# eLight.net
KiCad netlist of a schematic drawn in EasyEDA Pro
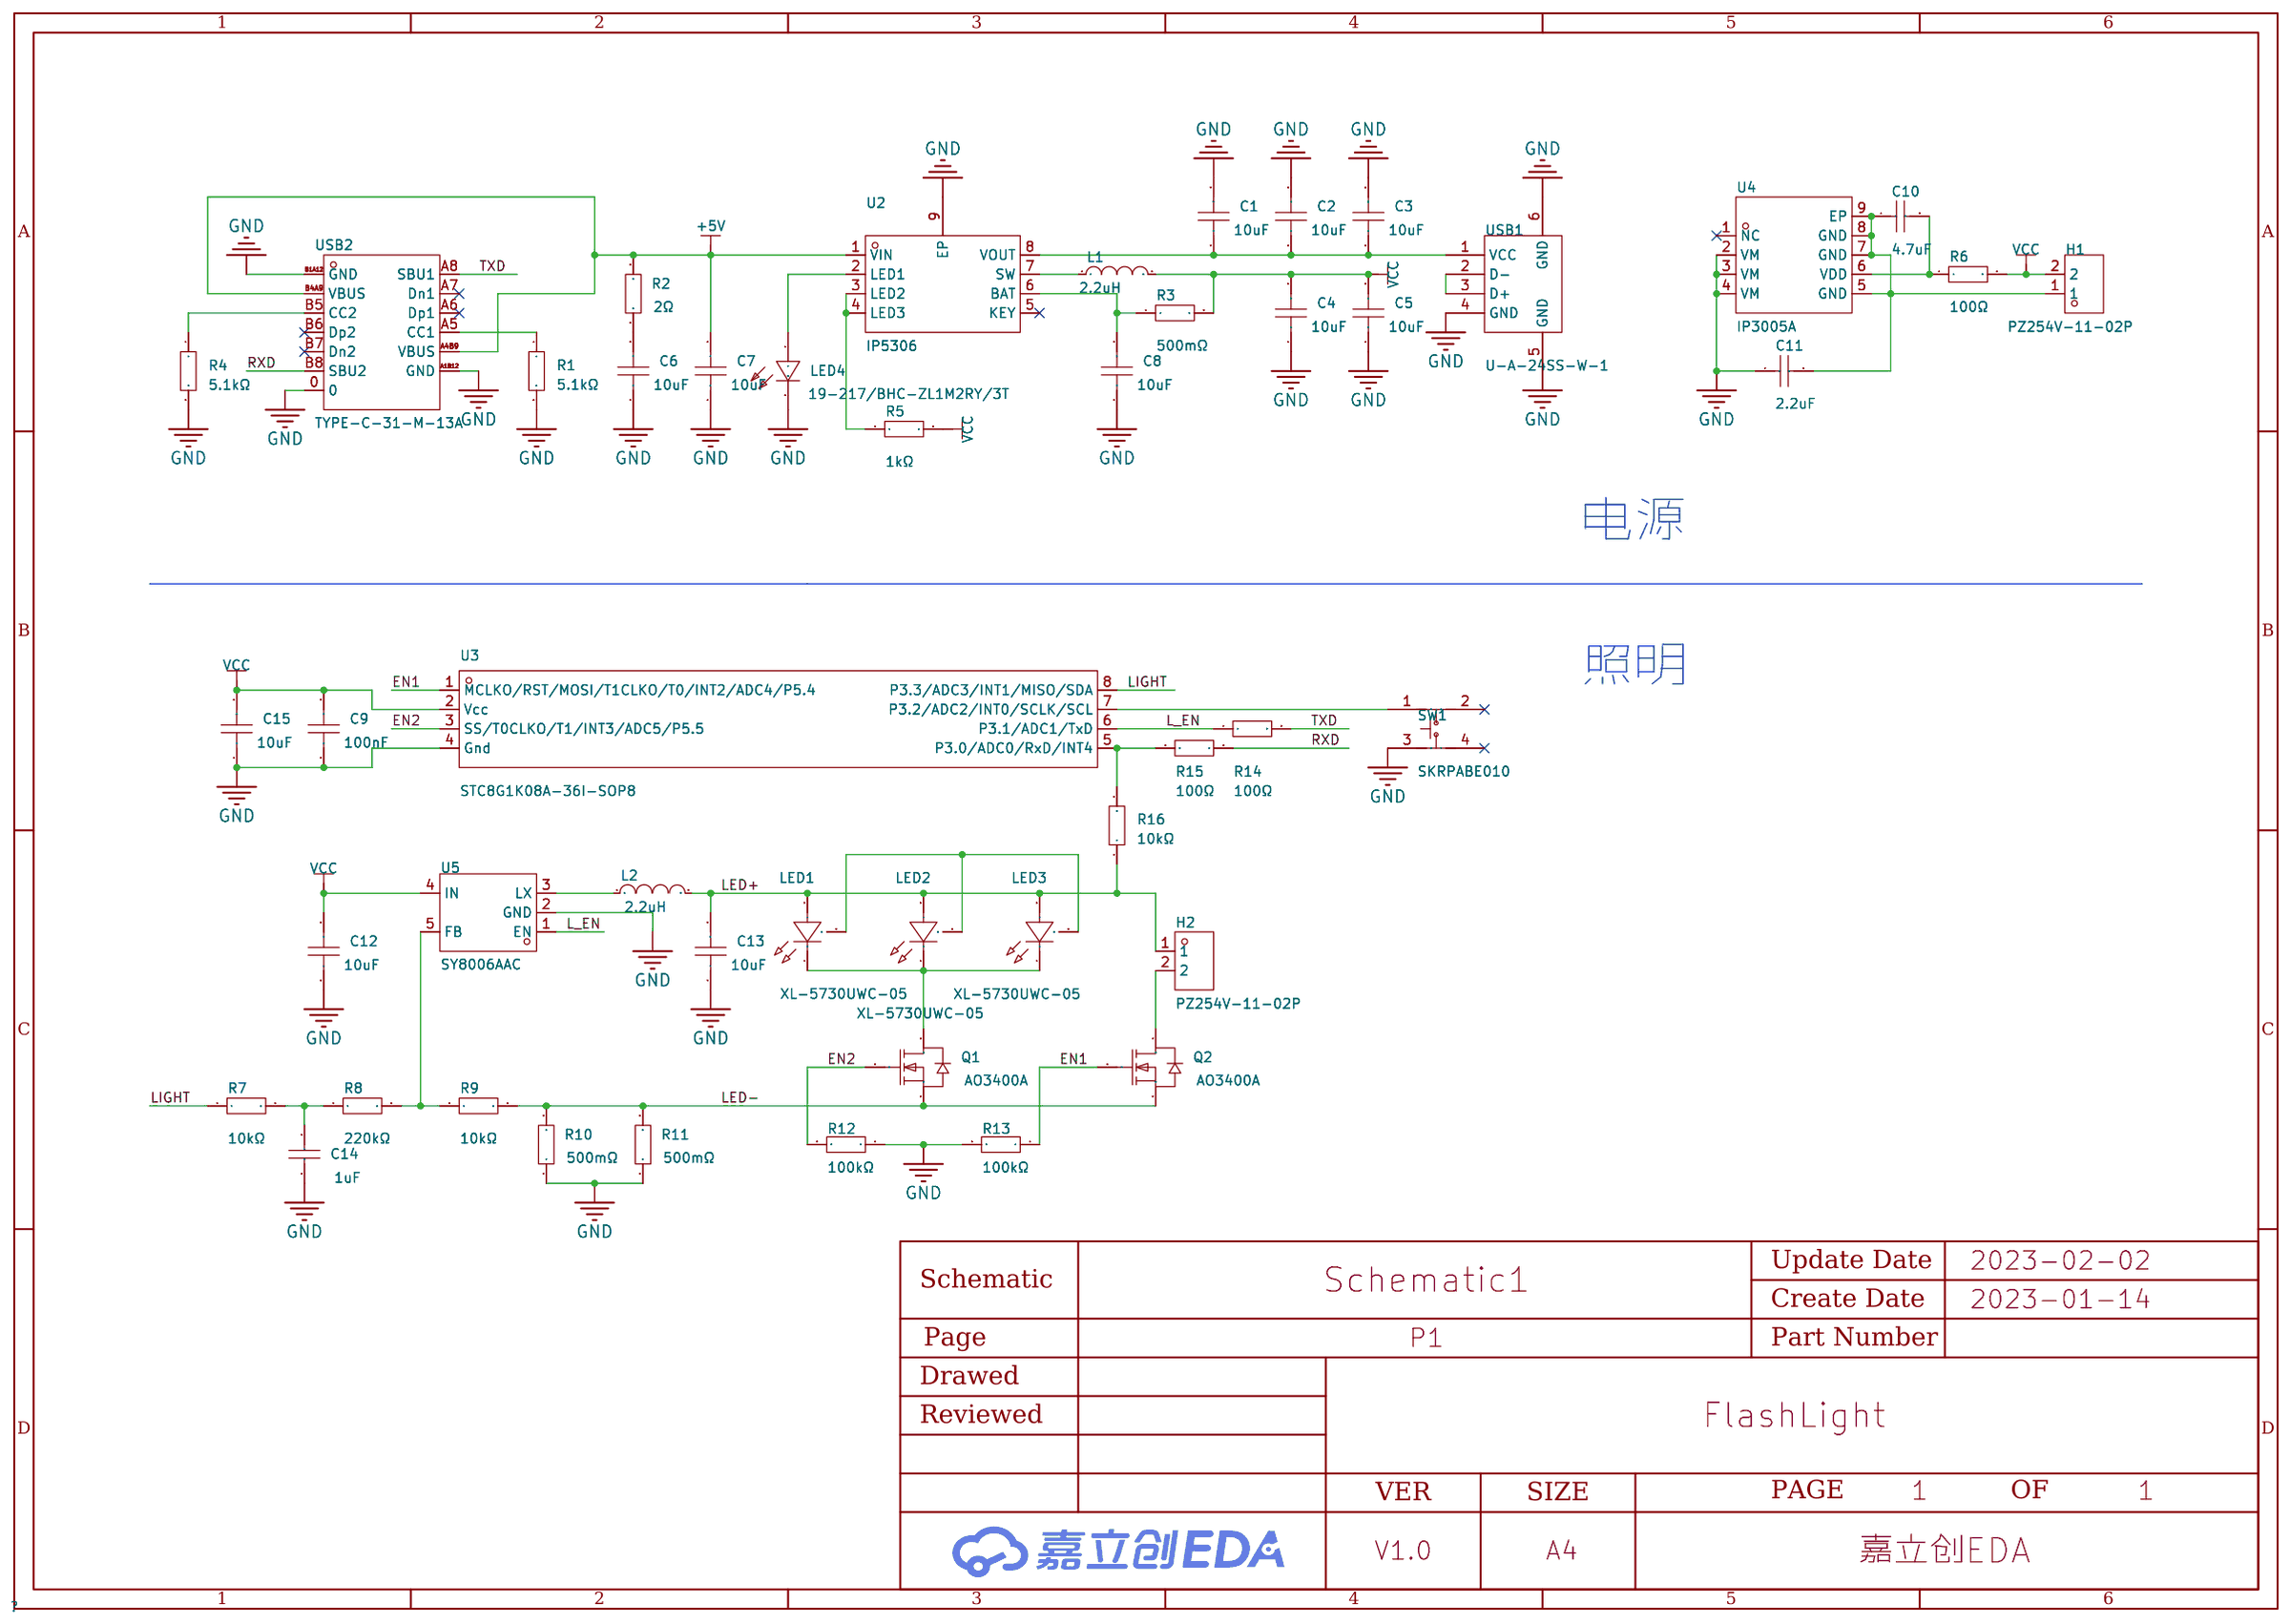
[diagram p0: schematic sheet]

(export (version "E")
  (design (tool "Eeschema 10.0.6"))
  (components
    (comp (ref "C1")
      (value "10uF")
      (footprint "easyedapro:C0603")
      (description "容值:10uF;精度:±10%;额定电压:10V;材质(温度系数):X5R;")
      (fields
        (field (name "Manufacturer Part") "CL10A106KP8NNNC")
        (field (name "Manufacturer") "SAMSUNG(三星)")
      )
      (libsource (lib "easyedapro") (part "CL10A106KP8NNNC"))
    )
    (comp (ref "C2")
      (value "10uF")
      (footprint "easyedapro:C0603")
      (description "容值:10uF;精度:±10%;额定电压:10V;材质(温度系数):X5R;")
      (fields
        (field (name "Manufacturer Part") "CL10A106KP8NNNC")
        (field (name "Manufacturer") "SAMSUNG(三星)")
      )
      (libsource (lib "easyedapro") (part "CL10A106KP8NNNC"))
    )
    (comp (ref "C3")
      (value "10uF")
      (footprint "easyedapro:C0603")
      (description "容值:10uF;精度:±10%;额定电压:10V;材质(温度系数):X5R;")
      (fields
        (field (name "Manufacturer Part") "CL10A106KP8NNNC")
        (field (name "Manufacturer") "SAMSUNG(三星)")
      )
      (libsource (lib "easyedapro") (part "CL10A106KP8NNNC"))
    )
    (comp (ref "C4")
      (value "10uF")
      (footprint "easyedapro:C0603")
      (description "容值:10uF;精度:±10%;额定电压:10V;材质(温度系数):X5R;")
      (fields
        (field (name "Manufacturer Part") "CL10A106KP8NNNC")
        (field (name "Manufacturer") "SAMSUNG(三星)")
      )
      (libsource (lib "easyedapro") (part "CL10A106KP8NNNC"))
    )
    (comp (ref "C5")
      (value "10uF")
      (footprint "easyedapro:C0603")
      (description "容值:10uF;精度:±10%;额定电压:10V;材质(温度系数):X5R;")
      (fields
        (field (name "Manufacturer Part") "CL10A106KP8NNNC")
        (field (name "Manufacturer") "SAMSUNG(三星)")
      )
      (libsource (lib "easyedapro") (part "CL10A106KP8NNNC"))
    )
    (comp (ref "C6")
      (value "10uF")
      (footprint "easyedapro:C0603")
      (description "容值:10uF;精度:±10%;额定电压:10V;材质(温度系数):X5R;")
      (fields
        (field (name "Manufacturer Part") "CL10A106KP8NNNC")
        (field (name "Manufacturer") "SAMSUNG(三星)")
      )
      (libsource (lib "easyedapro") (part "CL10A106KP8NNNC"))
    )
    (comp (ref "C7")
      (value "10uF")
      (footprint "easyedapro:C0603")
      (description "容值:10uF;精度:±10%;额定电压:10V;材质(温度系数):X5R;")
      (fields
        (field (name "Manufacturer Part") "CL10A106KP8NNNC")
        (field (name "Manufacturer") "SAMSUNG(三星)")
      )
      (libsource (lib "easyedapro") (part "CL10A106KP8NNNC"))
    )
    (comp (ref "C8")
      (value "10uF")
      (footprint "easyedapro:C0603")
      (description "容值:10uF;精度:±10%;额定电压:10V;材质(温度系数):X5R;")
      (fields
        (field (name "Manufacturer Part") "CL10A106KP8NNNC")
        (field (name "Manufacturer") "SAMSUNG(三星)")
      )
      (libsource (lib "easyedapro") (part "CL10A106KP8NNNC"))
    )
    (comp (ref "C9")
      (value "100nF")
      (footprint "easyedapro:C0603")
      (description "容值:100nF;精度:±10%;额定电压:50V;材质(温度系数):X7R;")
      (fields
        (field (name "Manufacturer Part") "CC0603KRX7R9BB104")
        (field (name "Manufacturer") "YAGEO(国巨)")
      )
      (libsource (lib "easyedapro") (part "CC0603KRX7R9BB104"))
    )
    (comp (ref "C10")
      (value "4.7uF")
      (footprint "easyedapro:C0603")
      (description "容值:4.7uF;精度:±10%;额定电压:16V;材质(温度系数):X5R;")
      (fields
        (field (name "Manufacturer Part") "CL10A475KO8NNNC")
        (field (name "Manufacturer") "SAMSUNG(三星)")
      )
      (libsource (lib "easyedapro") (part "CL10A475KO8NNNC"))
    )
    (comp (ref "C11")
      (value "2.2uF")
      (footprint "easyedapro:C0603")
      (description "容值:2.2uF;精度:±10%;额定电压:16V;材质(温度系数):X5R;")
      (fields
        (field (name "Manufacturer Part") "CL10A225KO8NNNC")
        (field (name "Manufacturer") "SAMSUNG(三星)")
      )
      (libsource (lib "easyedapro") (part "CL10A225KO8NNNC"))
    )
    (comp (ref "C12")
      (value "10uF")
      (footprint "easyedapro:C0603")
      (description "容值:10uF;精度:±10%;额定电压:10V;材质(温度系数):X5R;")
      (fields
        (field (name "Manufacturer Part") "CL10A106KP8NNNC")
        (field (name "Manufacturer") "SAMSUNG(三星)")
      )
      (libsource (lib "easyedapro") (part "CL10A106KP8NNNC"))
    )
    (comp (ref "C13")
      (value "10uF")
      (footprint "easyedapro:C0603")
      (description "容值:10uF;精度:±10%;额定电压:10V;材质(温度系数):X5R;")
      (fields
        (field (name "Manufacturer Part") "CL10A106KP8NNNC")
        (field (name "Manufacturer") "SAMSUNG(三星)")
      )
      (libsource (lib "easyedapro") (part "CL10A106KP8NNNC"))
    )
    (comp (ref "C14")
      (value "1uF")
      (footprint "easyedapro:C0603")
      (description "容值:1uF;精度:±10%;额定电压:50V;材质(温度系数):X5R;")
      (fields
        (field (name "Manufacturer Part") "CL10A105KB8NNNC")
        (field (name "Manufacturer") "SAMSUNG(三星)")
      )
      (libsource (lib "easyedapro") (part "CL10A105KB8NNNC"))
    )
    (comp (ref "C15")
      (value "10uF")
      (footprint "easyedapro:C0603")
      (description "容值:10uF;精度:±10%;额定电压:10V;材质(温度系数):X5R;")
      (fields
        (field (name "Manufacturer Part") "CL10A106KP8NNNC")
        (field (name "Manufacturer") "SAMSUNG(三星)")
      )
      (libsource (lib "easyedapro") (part "CL10A106KP8NNNC"))
    )
    (comp (ref "H1")
      (value "PZ254V-11-02P")
      (footprint "easyedapro:HDR-TH_2P-P2.54-V-M")
      (fields (field (name "Manufacturer") "XFCN(兴飞)"))
      (libsource (lib "easyedapro") (part "PZ254V-11-02P"))
    )
    (comp (ref "H2")
      (value "PZ254V-11-02P")
      (footprint "easyedapro:HDR-TH_2P-P2.54-V-M")
      (fields (field (name "Manufacturer") "XFCN(兴飞)"))
      (libsource (lib "easyedapro") (part "PZ254V-11-02P"))
    )
    (comp (ref "L1")
      (value "2.2uH")
      (footprint "easyedapro:IND-SMD_L7.3-W6.6")
      (description "电感值:2.2uH;精度:±20%;额定电流:8A;饱和电流(Isat):12A;直流电阻(DCR):17mΩ;")
      (fields (field (name "Manufacturer Part") "MCS0630-2R2MPY1") (field (name "Manufacturer") "PSA(信昌电陶)"))
      (libsource (lib "easyedapro") (part "MCS0630-2R2MPY1"))
    )
    (comp (ref "L2")
      (value "2.2uH")
      (footprint "easyedapro:IND-SMD_L4.5-W4.0-1")
      (description "电感值:2.2uH;精度:±20%;额定电流:3A;直流电阻(DCR):52mΩ;")
      (fields (field (name "Manufacturer Part") "MCS0420-2R2MN2") (field (name "Manufacturer") "PSA(信昌电陶)"))
      (libsource (lib "easyedapro") (part "MCS0420-2R2MN2"))
    )
    (comp (ref "LED1")
      (value "XL-5730UWC-05")
      (footprint "easyedapro:LED-SMD_3P-L5.7-W3.0-RD")
      (fields (field (name "Manufacturer") "XINGLIGHT(成兴光)"))
      (libsource (lib "easyedapro") (part "XL-5730UWC-05"))
    )
    (comp (ref "LED2")
      (value "XL-5730UWC-05")
      (footprint "easyedapro:LED-SMD_3P-L5.7-W3.0-RD")
      (fields (field (name "Manufacturer") "XINGLIGHT(成兴光)"))
      (libsource (lib "easyedapro") (part "XL-5730UWC-05"))
    )
    (comp (ref "LED3")
      (value "XL-5730UWC-05")
      (footprint "easyedapro:LED-SMD_3P-L5.7-W3.0-RD")
      (fields (field (name "Manufacturer") "XINGLIGHT(成兴光)"))
      (libsource (lib "easyedapro") (part "XL-5730UWC-05"))
    )
    (comp (ref "LED4")
      (value "19-217/BHC-ZL1M2RY/3T")
      (footprint "easyedapro:LED0603-R-RD_BLUE")
      (description "照明颜色:蓝色;主波长/色坐标:465~475nm;")
      (fields (field (name "Manufacturer") "EVERLIGHT(亿光)"))
      (libsource (lib "easyedapro") (part "19-217/BHC-ZL1M2RY/3T"))
    )
    (comp (ref "Q1")
      (value "AO3400A")
      (footprint "easyedapro:SOT-23-3_L2.9-W1.6-P1.90-LS2.8-BR")
      (fields (field (name "Manufacturer") "AOS"))
      (libsource (lib "easyedapro") (part "AO3400A"))
    )
    (comp (ref "Q2")
      (value "AO3400A")
      (footprint "easyedapro:SOT-23-3_L2.9-W1.6-P1.90-LS2.8-BR")
      (fields (field (name "Manufacturer") "AOS"))
      (libsource (lib "easyedapro") (part "AO3400A"))
    )
    (comp (ref "R1")
      (value "5.1kΩ")
      (footprint "easyedapro:R0603")
      (description "电阻类型:厚膜电阻;阻值:5.1kΩ;精度:±1%;功率:100mW;温度系数:±100ppm/℃;最大工作电压:75V;工作温度范围:-55℃~+155℃;")
      (fields
        (field (name "Manufacturer Part") "0603WAF5101T5E")
        (field (name "Manufacturer") "UNI-ROYAL(厚声)")
      )
      (libsource (lib "easyedapro") (part "0603WAF5101T5E"))
    )
    (comp (ref "R2")
      (value "2Ω")
      (footprint "easyedapro:R0603")
      (description "电阻类型:厚膜电阻;阻值:2Ω;精度:±1%;功率:100mW;温度系数:±400ppm/℃;最大工作电压:75V;工作温度范围:-55℃~+155℃;")
      (fields
        (field (name "Manufacturer Part") "0603WAF200KT5E")
        (field (name "Manufacturer") "UNI-ROYAL(厚声)")
      )
      (libsource (lib "easyedapro") (part "0603WAF200KT5E"))
    )
    (comp (ref "R3")
      (value "500mΩ")
      (footprint "easyedapro:R0603")
      (description "电阻类型:厚膜电阻;阻值:510mΩ;精度:±1%;功率:100mW;温度系数:±800ppm/°C;最大工作电压:75V;工作温度范围:-55°C~+155°C;")
      (fields
        (field (name "Manufacturer Part") "0603WAF500LT5E")
        (field (name "Manufacturer") "UNI-ROYAL(厚声)")
      )
      (libsource (lib "easyedapro") (part "0603WAF510LT5E"))
    )
    (comp (ref "R4")
      (value "5.1kΩ")
      (footprint "easyedapro:R0603")
      (description "电阻类型:厚膜电阻;阻值:5.1kΩ;精度:±1%;功率:100mW;温度系数:±100ppm/°C;最大工作电压:75V;工作温度范围:-55°C~+155°C;")
      (fields
        (field (name "Manufacturer Part") "0603WAF5101T5E")
        (field (name "Manufacturer") "UNI-ROYAL(厚声)")
      )
      (libsource (lib "easyedapro") (part "0603WAF5101T5E"))
    )
    (comp (ref "R5")
      (value "1kΩ")
      (footprint "easyedapro:R0603")
      (description "电阻类型:厚膜电阻;阻值:1kΩ;精度:±1%;功率:100mW;温度系数:±100ppm/°C;最大工作电压:75V;工作温度范围:-55°C~+155°C;")
      (fields
        (field (name "Manufacturer Part") "0603WAF1001T5E")
        (field (name "Manufacturer") "UNI-ROYAL(厚声)")
      )
      (libsource (lib "easyedapro") (part "0603WAF1001T5E"))
    )
    (comp (ref "R6")
      (value "100Ω")
      (footprint "easyedapro:R0603")
      (description "电阻类型:厚膜电阻;阻值:100Ω;精度:±1%;功率:100mW;温度系数:±200ppm/°C;最大工作电压:75V;工作温度范围:-55°C~+155°C;")
      (fields
        (field (name "Manufacturer Part") "0603WAF1000T5E")
        (field (name "Manufacturer") "UNI-ROYAL(厚声)")
      )
      (libsource (lib "easyedapro") (part "0603WAF1000T5E"))
    )
    (comp (ref "R7")
      (value "10kΩ")
      (footprint "easyedapro:R0603")
      (description "电阻类型:厚膜电阻;阻值:10kΩ;精度:±1%;功率:100mW;温度系数:±100ppm/°C;最大工作电压:75V;工作温度范围:-55°C~+155°C;")
      (fields
        (field (name "Manufacturer Part") "0603WAF1002T5E")
        (field (name "Manufacturer") "UNI-ROYAL(厚声)")
      )
      (libsource (lib "easyedapro") (part "0603WAF1002T5E"))
    )
    (comp (ref "R8")
      (value "220kΩ")
      (footprint "easyedapro:R0603")
      (description "电阻类型:厚膜电阻;阻值:100kΩ;精度:±1%;功率:100mW;温度系数:±100ppm/°C;最大工作电压:75V;工作温度范围:-55°C~+155°C;")
      (fields
        (field (name "Manufacturer Part") "0603WAF2203T5E")
        (field (name "Manufacturer") "UNI-ROYAL(厚声)")
      )
      (libsource (lib "easyedapro") (part "0603WAF1003T5E"))
    )
    (comp (ref "R9")
      (value "10kΩ")
      (footprint "easyedapro:R0603")
      (description "电阻类型:厚膜电阻;阻值:10kΩ;精度:±1%;功率:100mW;温度系数:±100ppm/°C;最大工作电压:75V;工作温度范围:-55°C~+155°C;")
      (fields
        (field (name "Manufacturer Part") "0603WAF1002T5E")
        (field (name "Manufacturer") "UNI-ROYAL(厚声)")
      )
      (libsource (lib "easyedapro") (part "0603WAF1002T5E"))
    )
    (comp (ref "R10")
      (value "500mΩ")
      (footprint "easyedapro:R0805")
      (description "电阻类型:厚膜电阻;阻值:500mΩ;精度:±1%;功率:125mW;温度系数:±800ppm/℃;最大工作电压:150V;工作温度范围:-55℃~+155℃;")
      (fields
        (field (name "Manufacturer Part") "0805W8F500LT5E")
        (field (name "Manufacturer") "UNI-ROYAL(厚声)")
      )
      (libsource (lib "easyedapro") (part "0805W8F510LT5E"))
    )
    (comp (ref "R11")
      (value "500mΩ")
      (footprint "easyedapro:R0805")
      (description "电阻类型:厚膜电阻;阻值:510mΩ;精度:±1%;功率:125mW;温度系数:±800ppm/°C;最大工作电压:150V;工作温度范围:-55°C~+155°C;")
      (fields
        (field (name "Manufacturer Part") "0805W8F500LT5E")
        (field (name "Manufacturer") "UNI-ROYAL(厚声)")
      )
      (libsource (lib "easyedapro") (part "0805W8F510LT5E"))
    )
    (comp (ref "R12")
      (value "100kΩ")
      (footprint "easyedapro:R0603")
      (description "电阻类型:厚膜电阻;阻值:10kΩ;精度:±1%;功率:100mW;温度系数:±100ppm/°C;最大工作电压:75V;工作温度范围:-55°C~+155°C;")
      (fields
        (field (name "Manufacturer Part") "0603WAF1003T5E")
        (field (name "Manufacturer") "UNI-ROYAL(厚声)")
      )
      (libsource (lib "easyedapro") (part "0603WAF1002T5E"))
    )
    (comp (ref "R13")
      (value "100kΩ")
      (footprint "easyedapro:R0603")
      (description "电阻类型:厚膜电阻;阻值:10kΩ;精度:±1%;功率:100mW;温度系数:±100ppm/°C;最大工作电压:75V;工作温度范围:-55°C~+155°C;")
      (fields
        (field (name "Manufacturer Part") "0603WAF1003T5E")
        (field (name "Manufacturer") "UNI-ROYAL(厚声)")
      )
      (libsource (lib "easyedapro") (part "0603WAF1002T5E"))
    )
    (comp (ref "R14")
      (value "100Ω")
      (footprint "easyedapro:R0603")
      (description "电阻类型:厚膜电阻;阻值:100Ω;精度:±1%;功率:100mW;温度系数:±200ppm/°C;最大工作电压:75V;工作温度范围:-55°C~+155°C;")
      (fields
        (field (name "Manufacturer Part") "0603WAF1000T5E")
        (field (name "Manufacturer") "UNI-ROYAL(厚声)")
      )
      (libsource (lib "easyedapro") (part "0603WAF1000T5E"))
    )
    (comp (ref "R15")
      (value "100Ω")
      (footprint "easyedapro:R0603")
      (description "电阻类型:厚膜电阻;阻值:100Ω;精度:±1%;功率:100mW;温度系数:±200ppm/°C;最大工作电压:75V;工作温度范围:-55°C~+155°C;")
      (fields
        (field (name "Manufacturer Part") "0603WAF1000T5E")
        (field (name "Manufacturer") "UNI-ROYAL(厚声)")
      )
      (libsource (lib "easyedapro") (part "0603WAF1000T5E"))
    )
    (comp (ref "R16")
      (value "10kΩ")
      (footprint "easyedapro:R0603")
      (description "电阻类型:厚膜电阻;阻值:10kΩ;精度:±1%;功率:100mW;温度系数:±100ppm/°C;最大工作电压:75V;工作温度范围:-55°C~+155°C;")
      (fields
        (field (name "Manufacturer Part") "0603WAF1002T5E")
        (field (name "Manufacturer") "UNI-ROYAL(厚声)")
      )
      (libsource (lib "easyedapro") (part "0603WAF1002T5E"))
    )
    (comp (ref "SW1")
      (value "SKRPABE010")
      (footprint "easyedapro:KEY-SMD_4P-L4.2-W3.2-P2.20-LS4.6")
      (description "触点电流:50mA;额定电压(DC):16V;电路结构:单刀单掷;按钮作用方向:顶部触动;致动器样式:椭圆形按钮;照明颜色:-;开关长度:4.2mm;开关宽度:3.2mm;开关高度:2.5mm;")
      (fields (field (name "Manufacturer") "ALPSALPINE(阿尔卑斯阿尔派)"))
      (libsource (lib "easyedapro") (part "SKRPABE010"))
    )
    (comp (ref "U2")
      (value "IP5306")
      (footprint "easyedapro:ESOP-8_L4.9-W3.9-P1.27-LS6.0-BL-EP")
      (description "2.1A充电2.4A放电高集成度移动电源SOC")
      (fields (field (name "Manufacturer") "INJOINIC(英集芯)"))
      (libsource (lib "easyedapro") (part "IP5306"))
    )
    (comp (ref "U3")
      (value "STC8G1K08A-36I-SOP8")
      (footprint "easyedapro:SOP-8_L5.0-W4.0-P1.27-LS6.0-BL")
      (fields (field (name "Manufacturer") "STC(宏晶)"))
      (libsource (lib "easyedapro") (part "STC8G1K08A-36I-SOP8"))
    )
    (comp (ref "U4")
      (value "IP3005A")
      (footprint "easyedapro:ESOP-8_L4.9-W3.9-P1.27-LS6.0-BL-EP")
      (description "过充电压:4.28V,过充恢复电压:4.1V,高精度内置MOSFET单节锂电池保护IC")
      (fields (field (name "Manufacturer") "INJOINIC(英集芯)"))
      (libsource (lib "easyedapro") (part "IP3005A"))
    )
    (comp (ref "U5")
      (value "SY8006AAC")
      (footprint "easyedapro:SOT-23-5_L3.0-W1.6-P0.95-LS2.8-BR")
      (fields (field (name "Manufacturer") "silergy(矽力杰)"))
      (libsource (lib "easyedapro") (part "SY8006AAC"))
    )
    (comp (ref "USB1")
      (value "U-A-24SS-W-1")
      (footprint "easyedapro:USB-A-SMD_U-A-24SS-W-1")
      (description "连接器类型:Type-A;标准:USB 2.0;公母:母座;触点数量:4;端口数量:1;额定电流 - 电源:-;")
      (fields (field (name "Manufacturer") "韩国韩荣"))
      (libsource (lib "easyedapro") (part "U-A-24SS-W-1"))
    )
    (comp (ref "USB2")
      (value "TYPE-C-31-M-13A")
      (footprint "easyedapro:USB-C-SMD_TYPE-C-31-M-13A-1")
      (fields (field (name "Manufacturer") "韩国韩荣"))
      (libsource (lib "easyedapro") (part "TYPE-C-31-M-13A"))
    )
  )
  (nets
    (net (code "1") (name "+5V") (class "Default")
      (node (ref "C7") (pin "2") (pinfunction "2_2") (pintype "input"))
      (node (ref "R2") (pin "2") (pinfunction "2_2") (pintype "input"))
      (node (ref "U2") (pin "1") (pinfunction "VIN_1") (pintype "input"))
      (node (ref "USB2") (pin "A4B9") (pinfunction "VBUS_A4B9") (pintype "input"))
      (node (ref "USB2") (pin "B4A9") (pinfunction "VBUS_B4A9") (pintype "input"))
    )
    (net (code "2") (name "/EN1") (class "Default")
      (node (ref "Q2") (pin "1") (pinfunction "G_1") (pintype "input"))
      (node (ref "R13") (pin "1") (pinfunction "1_1") (pintype "input"))
      (node (ref "U3") (pin "1") (pinfunction "MCLKO/RST/MOSI/T1CLKO/T0/INT2/ADC4/P5.4_1") (pintype "input"))
    )
    (net (code "3") (name "/EN2") (class "Default")
      (node (ref "Q1") (pin "1") (pinfunction "G_1") (pintype "input"))
      (node (ref "R12") (pin "2") (pinfunction "2_2") (pintype "input"))
      (node (ref "U3") (pin "3") (pinfunction "SS/T0CLKO/T1/INT3/ADC5/P5.5_3") (pintype "input"))
    )
    (net (code "4") (name "/LED+") (class "Default")
      (node (ref "C13") (pin "2") (pinfunction "2_2") (pintype "input"))
      (node (ref "H2") (pin "1") (pinfunction "1_1") (pintype "input"))
      (node (ref "L2") (pin "2") (pinfunction "2_2") (pintype "input"))
      (node (ref "LED1") (pin "2") (pinfunction "A_2") (pintype "input"))
      (node (ref "LED2") (pin "2") (pinfunction "A_2") (pintype "input"))
      (node (ref "LED3") (pin "2") (pinfunction "A_2") (pintype "input"))
      (node (ref "R16") (pin "1") (pinfunction "1_1") (pintype "input"))
    )
    (net (code "5") (name "/LED-") (class "Default")
      (node (ref "Q1") (pin "2") (pinfunction "S_2") (pintype "input"))
      (node (ref "Q2") (pin "2") (pinfunction "S_2") (pintype "input"))
      (node (ref "R10") (pin "2") (pinfunction "2_2") (pintype "input"))
      (node (ref "R11") (pin "2") (pinfunction "2_2") (pintype "input"))
      (node (ref "R9") (pin "2") (pinfunction "2_2") (pintype "input"))
    )
    (net (code "6") (name "/LIGHT") (class "Default")
      (node (ref "R7") (pin "1") (pinfunction "1_1") (pintype "input"))
      (node (ref "U3") (pin "8") (pinfunction "P3.3/ADC3/INT1/MISO/SDA_8") (pintype "input"))
    )
    (net (code "7") (name "/L_EN") (class "Default")
      (node (ref "R14") (pin "1") (pinfunction "1_1") (pintype "input"))
      (node (ref "U3") (pin "6") (pinfunction "P3.1/ADC1/TxD_6") (pintype "input"))
      (node (ref "U5") (pin "1") (pinfunction "EN_1") (pintype "input"))
    )
    (net (code "8") (name "/RXD") (class "Default")
      (node (ref "R15") (pin "2") (pinfunction "2_2") (pintype "input"))
      (node (ref "USB2") (pin "B8") (pinfunction "SBU2_B8") (pintype "input"))
    )
    (net (code "9") (name "/TXD") (class "Default")
      (node (ref "R14") (pin "2") (pinfunction "2_2") (pintype "input"))
      (node (ref "USB2") (pin "A8") (pinfunction "SBU1_A8") (pintype "input"))
    )
    (net (code "10") (name "GND") (class "Default")
      (node (ref "C1") (pin "2") (pinfunction "2_2") (pintype "input"))
      (node (ref "C11") (pin "1") (pinfunction "1_1") (pintype "input"))
      (node (ref "C12") (pin "1") (pinfunction "1_1") (pintype "input"))
      (node (ref "C13") (pin "1") (pinfunction "1_1") (pintype "input"))
      (node (ref "C14") (pin "1") (pinfunction "1_1") (pintype "input"))
      (node (ref "C15") (pin "1") (pinfunction "1_1") (pintype "input"))
      (node (ref "C2") (pin "2") (pinfunction "2_2") (pintype "input"))
      (node (ref "C3") (pin "2") (pinfunction "2_2") (pintype "input"))
      (node (ref "C4") (pin "1") (pinfunction "1_1") (pintype "input"))
      (node (ref "C5") (pin "1") (pinfunction "1_1") (pintype "input"))
      (node (ref "C6") (pin "1") (pinfunction "1_1") (pintype "input"))
      (node (ref "C7") (pin "1") (pinfunction "1_1") (pintype "input"))
      (node (ref "C8") (pin "1") (pinfunction "1_1") (pintype "input"))
      (node (ref "C9") (pin "1") (pinfunction "1_1") (pintype "input"))
      (node (ref "LED4") (pin "2") (pinfunction "C_2") (pintype "input"))
      (node (ref "R1") (pin "2") (pinfunction "2_2") (pintype "input"))
      (node (ref "R10") (pin "1") (pinfunction "1_1") (pintype "input"))
      (node (ref "R11") (pin "1") (pinfunction "1_1") (pintype "input"))
      (node (ref "R12") (pin "1") (pinfunction "1_1") (pintype "input"))
      (node (ref "R13") (pin "2") (pinfunction "2_2") (pintype "input"))
      (node (ref "R4") (pin "2") (pinfunction "2_2") (pintype "input"))
      (node (ref "SW1") (pin "3") (pinfunction "3_3") (pintype "input"))
      (node (ref "U2") (pin "9") (pinfunction "EP_9") (pintype "input"))
      (node (ref "U3") (pin "4") (pinfunction "Gnd_4") (pintype "input"))
      (node (ref "U4") (pin "2") (pinfunction "VM_2") (pintype "input"))
      (node (ref "U4") (pin "3") (pinfunction "VM_3") (pintype "input"))
      (node (ref "U4") (pin "4") (pinfunction "VM_4") (pintype "input"))
      (node (ref "U5") (pin "2") (pinfunction "GND_2") (pintype "input"))
      (node (ref "USB1") (pin "4") (pinfunction "GND_4") (pintype "input"))
      (node (ref "USB1") (pin "5") (pinfunction "GND_5") (pintype "input"))
      (node (ref "USB1") (pin "6") (pinfunction "GND_6") (pintype "input"))
      (node (ref "USB2") (pin "0") (pinfunction "0_0") (pintype "input"))
      (node (ref "USB2") (pin "A1B12") (pinfunction "GND_A1B12") (pintype "input"))
      (node (ref "USB2") (pin "B1A12") (pinfunction "GND_B1A12") (pintype "input"))
    )
    (net (code "11") (name "Net-(C6-Pad2)") (class "Default")
      (node (ref "C6") (pin "2") (pinfunction "2_2") (pintype "input"))
      (node (ref "R2") (pin "1") (pinfunction "1_1") (pintype "input"))
    )
    (net (code "12") (name "Net-(C14-Pad2)") (class "Default")
      (node (ref "C14") (pin "2") (pinfunction "2_2") (pintype "input"))
      (node (ref "R7") (pin "2") (pinfunction "2_2") (pintype "input"))
      (node (ref "R8") (pin "1") (pinfunction "1_1") (pintype "input"))
    )
    (net (code "13") (name "Net-(LED1-K)") (class "Default")
      (node (ref "LED1") (pin "1") (pinfunction "K_1") (pintype "input"))
      (node (ref "LED2") (pin "1") (pinfunction "K_1") (pintype "input"))
      (node (ref "LED3") (pin "1") (pinfunction "K_1") (pintype "input"))
      (node (ref "Q1") (pin "3") (pinfunction "D_3") (pintype "input"))
    )
    (net (code "14") (name "Net-(LED1-Pad3)") (class "Default")
      (node (ref "LED1") (pin "3") (pinfunction "3_3") (pintype "input"))
      (node (ref "LED2") (pin "3") (pinfunction "3_3") (pintype "input"))
      (node (ref "LED3") (pin "3") (pinfunction "3_3") (pintype "input"))
    )
    (net (code "15") (name "Net-(LED4-A)") (class "Default")
      (node (ref "LED4") (pin "1") (pinfunction "A_1") (pintype "input"))
      (node (ref "U2") (pin "2") (pinfunction "LED1_2") (pintype "input"))
    )
    (net (code "16") (name "Net-(Q2-D)") (class "Default")
      (node (ref "H2") (pin "2") (pinfunction "2_2") (pintype "input"))
      (node (ref "Q2") (pin "3") (pinfunction "D_3") (pintype "input"))
    )
    (net (code "17") (name "Net-(U2-BAT)") (class "Default")
      (node (ref "C8") (pin "2") (pinfunction "2_2") (pintype "input"))
      (node (ref "R3") (pin "1") (pinfunction "1_1") (pintype "input"))
      (node (ref "U2") (pin "6") (pinfunction "BAT_6") (pintype "input"))
    )
    (net (code "18") (name "Net-(U2-LED2)") (class "Default")
      (node (ref "R5") (pin "1") (pinfunction "1_1") (pintype "input"))
      (node (ref "U2") (pin "3") (pinfunction "LED2_3") (pintype "input"))
      (node (ref "U2") (pin "4") (pinfunction "LED3_4") (pintype "input"))
    )
    (net (code "19") (name "Net-(U2-SW)") (class "Default")
      (node (ref "L1") (pin "1") (pinfunction "1_1") (pintype "input"))
      (node (ref "U2") (pin "7") (pinfunction "SW_7") (pintype "input"))
    )
    (net (code "20") (name "Net-(U2-VOUT)") (class "Default")
      (node (ref "C1") (pin "1") (pinfunction "1_1") (pintype "input"))
      (node (ref "C2") (pin "1") (pinfunction "1_1") (pintype "input"))
      (node (ref "C3") (pin "1") (pinfunction "1_1") (pintype "input"))
      (node (ref "U2") (pin "8") (pinfunction "VOUT_8") (pintype "input"))
      (node (ref "USB1") (pin "1") (pinfunction "VCC_1") (pintype "input"))
    )
    (net (code "21") (name "Net-(U3-P3.0{slash}ADC0{slash}RxD{slash}INT4)") (class "Default")
      (node (ref "R15") (pin "1") (pinfunction "1_1") (pintype "input"))
      (node (ref "R16") (pin "2") (pinfunction "2_2") (pintype "input"))
      (node (ref "U3") (pin "5") (pinfunction "P3.0/ADC0/RxD/INT4_5") (pintype "input"))
    )
    (net (code "22") (name "Net-(U3-P3.2{slash}ADC2{slash}INT0{slash}SCLK{slash}SCL)") (class "Default")
      (node (ref "SW1") (pin "1") (pinfunction "1_1") (pintype "input"))
      (node (ref "U3") (pin "7") (pinfunction "P3.2/ADC2/INT0/SCLK/SCL_7") (pintype "input"))
    )
    (net (code "23") (name "Net-(U4-EP)") (class "Default")
      (node (ref "C10") (pin "1") (pinfunction "1_1") (pintype "input"))
      (node (ref "C11") (pin "2") (pinfunction "2_2") (pintype "input"))
      (node (ref "H1") (pin "1") (pinfunction "1_1") (pintype "input"))
      (node (ref "U4") (pin "5") (pinfunction "GND_5") (pintype "input"))
      (node (ref "U4") (pin "7") (pinfunction "GND_7") (pintype "input"))
      (node (ref "U4") (pin "8") (pinfunction "GND_8") (pintype "input"))
      (node (ref "U4") (pin "9") (pinfunction "EP_9") (pintype "input"))
    )
    (net (code "24") (name "Net-(U4-VDD)") (class "Default")
      (node (ref "C10") (pin "2") (pinfunction "2_2") (pintype "input"))
      (node (ref "R6") (pin "1") (pinfunction "1_1") (pintype "input"))
      (node (ref "U4") (pin "6") (pinfunction "VDD_6") (pintype "input"))
    )
    (net (code "25") (name "Net-(U5-FB)") (class "Default")
      (node (ref "R8") (pin "2") (pinfunction "2_2") (pintype "input"))
      (node (ref "R9") (pin "1") (pinfunction "1_1") (pintype "input"))
      (node (ref "U5") (pin "5") (pinfunction "FB_5") (pintype "input"))
    )
    (net (code "26") (name "Net-(U5-LX)") (class "Default")
      (node (ref "L2") (pin "1") (pinfunction "1_1") (pintype "input"))
      (node (ref "U5") (pin "3") (pinfunction "LX_3") (pintype "input"))
    )
    (net (code "27") (name "Net-(USB1-D+)") (class "Default")
      (node (ref "USB1") (pin "2") (pinfunction "D-_2") (pintype "input"))
      (node (ref "USB1") (pin "3") (pinfunction "D+_3") (pintype "input"))
    )
    (net (code "28") (name "Net-(USB2-CC1)") (class "Default")
      (node (ref "R1") (pin "1") (pinfunction "1_1") (pintype "input"))
      (node (ref "USB2") (pin "A5") (pinfunction "CC1_A5") (pintype "input"))
    )
    (net (code "29") (name "Net-(USB2-CC2)") (class "Default")
      (node (ref "R4") (pin "1") (pinfunction "1_1") (pintype "input"))
      (node (ref "USB2") (pin "B5") (pinfunction "CC2_B5") (pintype "input"))
    )
    (net (code "30") (name "VCC") (class "Default")
      (node (ref "C12") (pin "2") (pinfunction "2_2") (pintype "input"))
      (node (ref "C15") (pin "2") (pinfunction "2_2") (pintype "input"))
      (node (ref "C4") (pin "2") (pinfunction "2_2") (pintype "input"))
      (node (ref "C5") (pin "2") (pinfunction "2_2") (pintype "input"))
      (node (ref "C9") (pin "2") (pinfunction "2_2") (pintype "input"))
      (node (ref "H1") (pin "2") (pinfunction "2_2") (pintype "input"))
      (node (ref "L1") (pin "2") (pinfunction "2_2") (pintype "input"))
      (node (ref "R3") (pin "2") (pinfunction "2_2") (pintype "input"))
      (node (ref "R5") (pin "2") (pinfunction "2_2") (pintype "input"))
      (node (ref "R6") (pin "2") (pinfunction "2_2") (pintype "input"))
      (node (ref "U3") (pin "2") (pinfunction "Vcc_2") (pintype "input"))
      (node (ref "U5") (pin "4") (pinfunction "IN_4") (pintype "input"))
    )
    (net (code "31") (name "unconnected-(SW1-Pad2)") (class "Default")
      (node (ref "SW1") (pin "2") (pinfunction "2_2") (pintype "input+no_connect"))
    )
    (net (code "32") (name "unconnected-(SW1-Pad4)") (class "Default")
      (node (ref "SW1") (pin "4") (pinfunction "4_4") (pintype "input+no_connect"))
    )
    (net (code "33") (name "unconnected-(U2-KEY-Pad5)") (class "Default")
      (node (ref "U2") (pin "5") (pinfunction "KEY_5") (pintype "input+no_connect"))
    )
    (net (code "34") (name "unconnected-(U4-NC-Pad1)") (class "Default")
      (node (ref "U4") (pin "1") (pinfunction "NC_1") (pintype "input+no_connect"))
    )
    (net (code "35") (name "unconnected-(USB2-Dn1-PadA7)") (class "Default")
      (node (ref "USB2") (pin "A7") (pinfunction "Dn1_A7") (pintype "input+no_connect"))
    )
    (net (code "36") (name "unconnected-(USB2-Dn2-PadB7)") (class "Default")
      (node (ref "USB2") (pin "B7") (pinfunction "Dn2_B7") (pintype "input+no_connect"))
    )
    (net (code "37") (name "unconnected-(USB2-Dp1-PadA6)") (class "Default")
      (node (ref "USB2") (pin "A6") (pinfunction "Dp1_A6") (pintype "input+no_connect"))
    )
    (net (code "38") (name "unconnected-(USB2-Dp2-PadB6)") (class "Default")
      (node (ref "USB2") (pin "B6") (pinfunction "Dp2_B6") (pintype "input+no_connect"))
    )
  )
)
